# display_zm1325.net
KiCad netlist of a schematic drawn in EAGLE
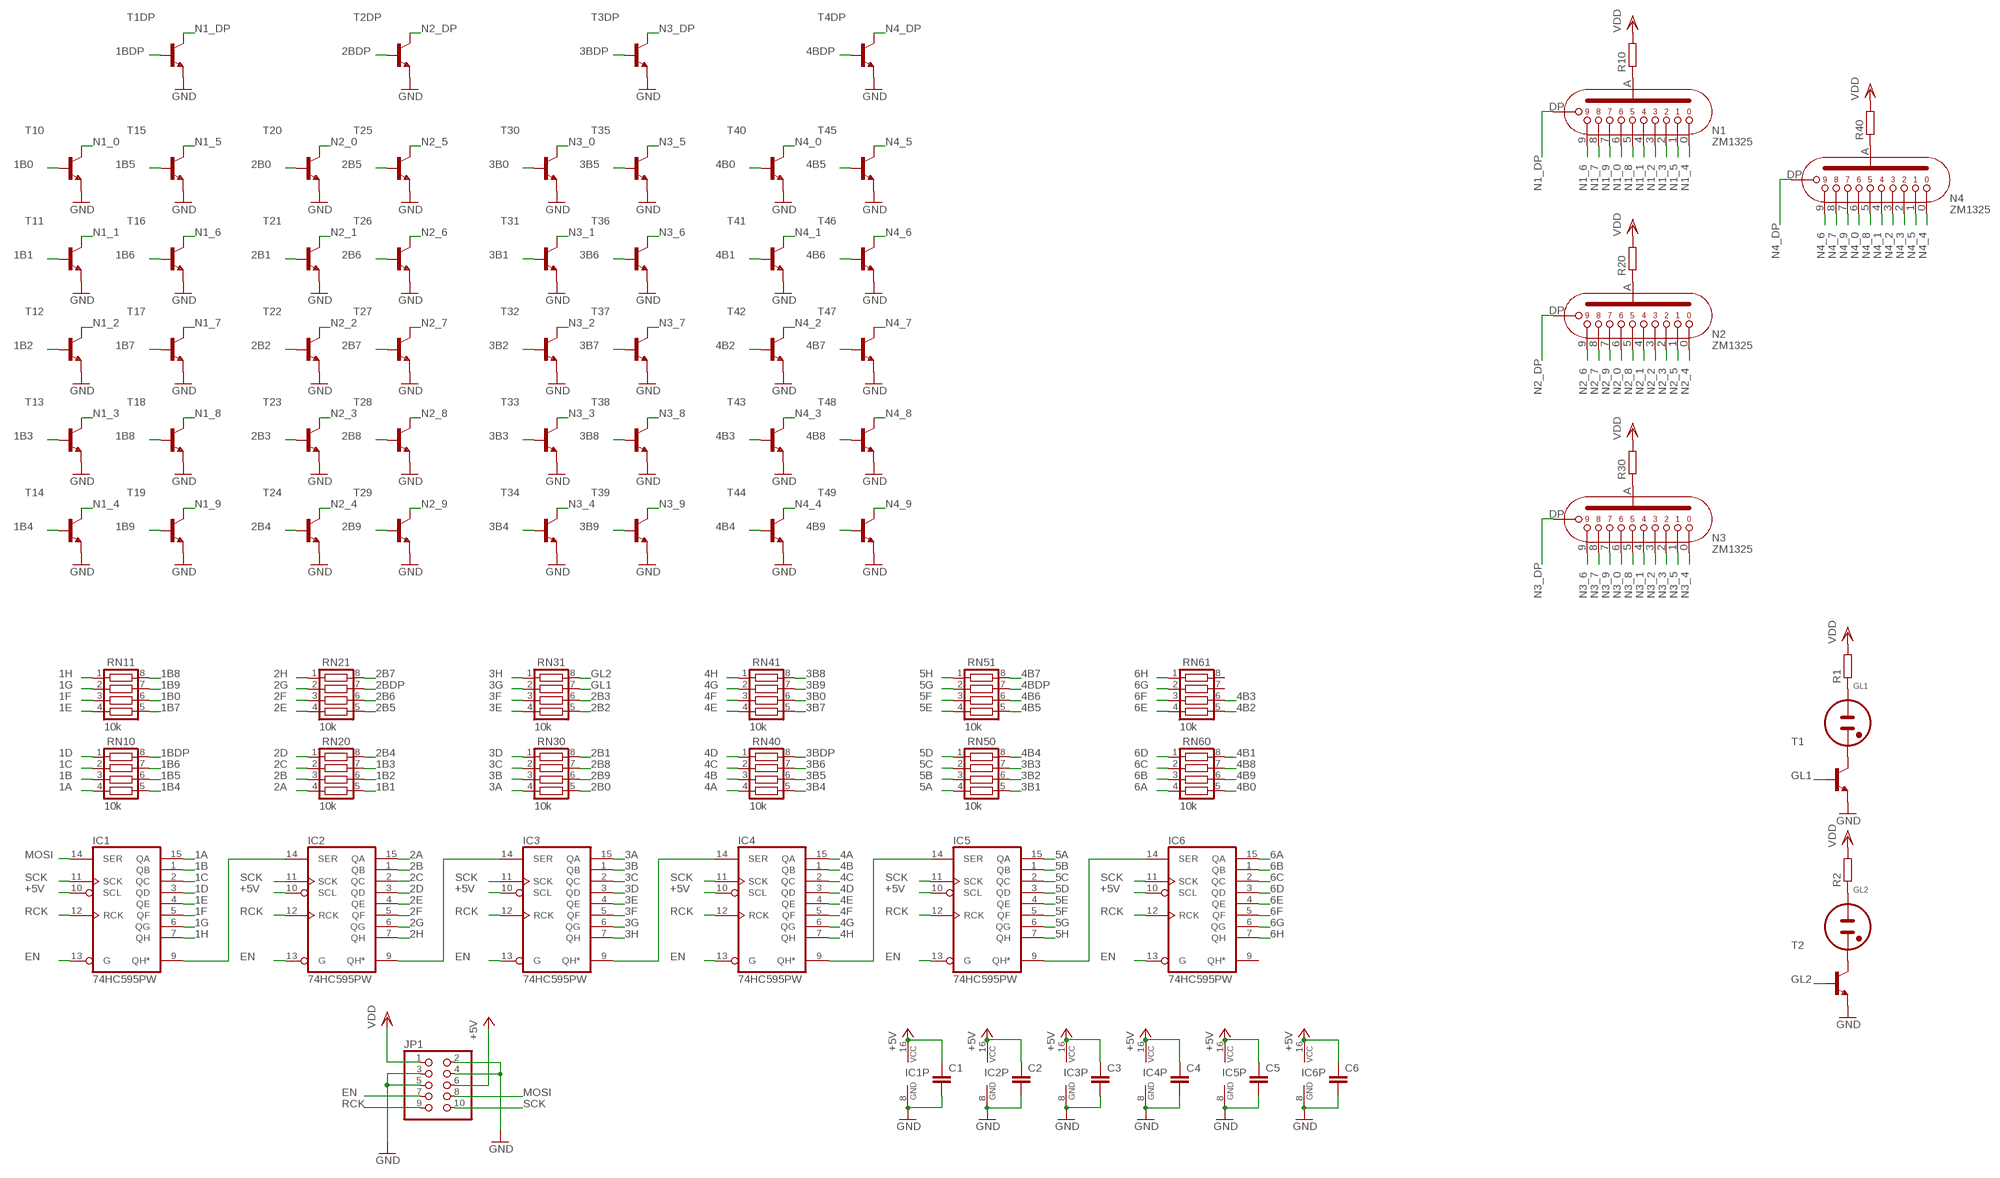
[diagram p0: schematic, sheet 1]

(export (version "E")
  (design (tool "Eeschema 10.0.6"))
  (components
    (comp (ref "C1")
      (value "C-EUC0603")
      (footprint "eagle-import:C0603")
      (libsource (lib "eagle-import") (part "C-EUC0603"))
    )
    (comp (ref "C2")
      (value "C-EUC0603")
      (footprint "eagle-import:C0603")
      (libsource (lib "eagle-import") (part "C-EUC0603"))
    )
    (comp (ref "C3")
      (value "C-EUC0603")
      (footprint "eagle-import:C0603")
      (libsource (lib "eagle-import") (part "C-EUC0603"))
    )
    (comp (ref "C4")
      (value "C-EUC0603")
      (footprint "eagle-import:C0603")
      (libsource (lib "eagle-import") (part "C-EUC0603"))
    )
    (comp (ref "C5")
      (value "C-EUC0603")
      (footprint "eagle-import:C0603")
      (libsource (lib "eagle-import") (part "C-EUC0603"))
    )
    (comp (ref "C6")
      (value "C-EUC0603")
      (footprint "eagle-import:C0603")
      (libsource (lib "eagle-import") (part "C-EUC0603"))
    )
    (comp (ref "GL1")
      (value "NE2-NEON-BULB-DRILL")
      (footprint "eagle-import:NE2-NEON-BULB-DRILL")
      (libsource (lib "eagle-import") (part "NE2-NEON-BULB-DRILL"))
    )
    (comp (ref "GL2")
      (value "NE2-NEON-BULB-DRILL")
      (footprint "eagle-import:NE2-NEON-BULB-DRILL")
      (libsource (lib "eagle-import") (part "NE2-NEON-BULB-DRILL"))
    )
    (comp (ref "IC1")
      (value "74HC595PW")
      (footprint "eagle-import:TSSOP16")
      (libsource (lib "eagle-import") (part "74595PWHC"))
    )
    (comp (ref "IC2")
      (value "74HC595PW")
      (footprint "eagle-import:TSSOP16")
      (libsource (lib "eagle-import") (part "74595PWHC"))
    )
    (comp (ref "IC3")
      (value "74HC595PW")
      (footprint "eagle-import:TSSOP16")
      (libsource (lib "eagle-import") (part "74595PWHC"))
    )
    (comp (ref "IC4")
      (value "74HC595PW")
      (footprint "eagle-import:TSSOP16")
      (libsource (lib "eagle-import") (part "74595PWHC"))
    )
    (comp (ref "IC5")
      (value "74HC595PW")
      (footprint "eagle-import:TSSOP16")
      (libsource (lib "eagle-import") (part "74595PWHC"))
    )
    (comp (ref "IC6")
      (value "74HC595PW")
      (footprint "eagle-import:TSSOP16")
      (libsource (lib "eagle-import") (part "74595PWHC"))
    )
    (comp (ref "JP1")
      (value "PINHD-2X5_2.54-SMD")
      (footprint "eagle-import:2X05SMD")
      (libsource (lib "eagle-import") (part "PINHD-2X5_2.54-SMD"))
    )
    (comp (ref "N1")
      (value "ZM1325")
      (footprint "eagle-import:ZM1325")
      (libsource (lib "eagle-import") (part "ZM1325"))
    )
    (comp (ref "N2")
      (value "ZM1325")
      (footprint "eagle-import:ZM1325")
      (libsource (lib "eagle-import") (part "ZM1325"))
    )
    (comp (ref "N3")
      (value "ZM1325")
      (footprint "eagle-import:ZM1325")
      (libsource (lib "eagle-import") (part "ZM1325"))
    )
    (comp (ref "N4")
      (value "ZM1325")
      (footprint "eagle-import:ZM1325")
      (libsource (lib "eagle-import") (part "ZM1325"))
    )
    (comp (ref "R1")
      (value "R-EU_R0603")
      (footprint "eagle-import:R0603")
      (libsource (lib "eagle-import") (part "R-EU_R0603"))
    )
    (comp (ref "R2")
      (value "R-EU_R0603")
      (footprint "eagle-import:R0603")
      (libsource (lib "eagle-import") (part "R-EU_R0603"))
    )
    (comp (ref "R10")
      (value "R-EU_R0603")
      (footprint "eagle-import:R0603")
      (libsource (lib "eagle-import") (part "R-EU_R0603"))
    )
    (comp (ref "R20")
      (value "R-EU_R0603")
      (footprint "eagle-import:R0603")
      (libsource (lib "eagle-import") (part "R-EU_R0603"))
    )
    (comp (ref "R30")
      (value "R-EU_R0603")
      (footprint "eagle-import:R0603")
      (libsource (lib "eagle-import") (part "R-EU_R0603"))
    )
    (comp (ref "R40")
      (value "R-EU_R0603")
      (footprint "eagle-import:R0603")
      (libsource (lib "eagle-import") (part "R-EU_R0603"))
    )
    (comp (ref "RN10")
      (value "10k")
      (footprint "eagle-import:CTS742C083")
      (fields (field (name "OC_FARNELL") "unknown") (field (name "OC_NEWARK") "unknown"))
      (libsource (lib "eagle-import") (part "CTS742C083"))
    )
    (comp (ref "RN11")
      (value "10k")
      (footprint "eagle-import:CTS742C083")
      (fields (field (name "OC_FARNELL") "unknown") (field (name "OC_NEWARK") "unknown"))
      (libsource (lib "eagle-import") (part "CTS742C083"))
    )
    (comp (ref "RN20")
      (value "10k")
      (footprint "eagle-import:CTS742C083")
      (fields (field (name "OC_FARNELL") "unknown") (field (name "OC_NEWARK") "unknown"))
      (libsource (lib "eagle-import") (part "CTS742C083"))
    )
    (comp (ref "RN21")
      (value "10k")
      (footprint "eagle-import:CTS742C083")
      (fields (field (name "OC_FARNELL") "unknown") (field (name "OC_NEWARK") "unknown"))
      (libsource (lib "eagle-import") (part "CTS742C083"))
    )
    (comp (ref "RN30")
      (value "10k")
      (footprint "eagle-import:CTS742C083")
      (fields (field (name "OC_FARNELL") "unknown") (field (name "OC_NEWARK") "unknown"))
      (libsource (lib "eagle-import") (part "CTS742C083"))
    )
    (comp (ref "RN31")
      (value "10k")
      (footprint "eagle-import:CTS742C083")
      (fields (field (name "OC_FARNELL") "unknown") (field (name "OC_NEWARK") "unknown"))
      (libsource (lib "eagle-import") (part "CTS742C083"))
    )
    (comp (ref "RN40")
      (value "10k")
      (footprint "eagle-import:CTS742C083")
      (fields (field (name "OC_FARNELL") "unknown") (field (name "OC_NEWARK") "unknown"))
      (libsource (lib "eagle-import") (part "CTS742C083"))
    )
    (comp (ref "RN41")
      (value "10k")
      (footprint "eagle-import:CTS742C083")
      (fields (field (name "OC_FARNELL") "unknown") (field (name "OC_NEWARK") "unknown"))
      (libsource (lib "eagle-import") (part "CTS742C083"))
    )
    (comp (ref "RN50")
      (value "10k")
      (footprint "eagle-import:CTS742C083")
      (fields (field (name "OC_FARNELL") "unknown") (field (name "OC_NEWARK") "unknown"))
      (libsource (lib "eagle-import") (part "CTS742C083"))
    )
    (comp (ref "RN51")
      (value "10k")
      (footprint "eagle-import:CTS742C083")
      (fields (field (name "OC_FARNELL") "unknown") (field (name "OC_NEWARK") "unknown"))
      (libsource (lib "eagle-import") (part "CTS742C083"))
    )
    (comp (ref "RN60")
      (value "10k")
      (footprint "eagle-import:CTS742C083")
      (fields (field (name "OC_FARNELL") "unknown") (field (name "OC_NEWARK") "unknown"))
      (libsource (lib "eagle-import") (part "CTS742C083"))
    )
    (comp (ref "RN61")
      (value "10k")
      (footprint "eagle-import:CTS742C083")
      (fields (field (name "OC_FARNELL") "unknown") (field (name "OC_NEWARK") "unknown"))
      (libsource (lib "eagle-import") (part "CTS742C083"))
    )
    (comp (ref "T1")
      (value "SMBTA42")
      (footprint "eagle-import:SOT23")
      (libsource (lib "eagle-import") (part "SMBTA42"))
    )
    (comp (ref "T1DP")
      (value "SMBTA42")
      (footprint "eagle-import:SOT23")
      (libsource (lib "eagle-import") (part "SMBTA42"))
    )
    (comp (ref "T2")
      (value "SMBTA42")
      (footprint "eagle-import:SOT23")
      (libsource (lib "eagle-import") (part "SMBTA42"))
    )
    (comp (ref "T2DP")
      (value "SMBTA42")
      (footprint "eagle-import:SOT23")
      (libsource (lib "eagle-import") (part "SMBTA42"))
    )
    (comp (ref "T3DP")
      (value "SMBTA42")
      (footprint "eagle-import:SOT23")
      (libsource (lib "eagle-import") (part "SMBTA42"))
    )
    (comp (ref "T4DP")
      (value "SMBTA42")
      (footprint "eagle-import:SOT23")
      (libsource (lib "eagle-import") (part "SMBTA42"))
    )
    (comp (ref "T10")
      (value "SMBTA42")
      (footprint "eagle-import:SOT23")
      (libsource (lib "eagle-import") (part "SMBTA42"))
    )
    (comp (ref "T11")
      (value "SMBTA42")
      (footprint "eagle-import:SOT23")
      (libsource (lib "eagle-import") (part "SMBTA42"))
    )
    (comp (ref "T12")
      (value "SMBTA42")
      (footprint "eagle-import:SOT23")
      (libsource (lib "eagle-import") (part "SMBTA42"))
    )
    (comp (ref "T13")
      (value "SMBTA42")
      (footprint "eagle-import:SOT23")
      (libsource (lib "eagle-import") (part "SMBTA42"))
    )
    (comp (ref "T14")
      (value "SMBTA42")
      (footprint "eagle-import:SOT23")
      (libsource (lib "eagle-import") (part "SMBTA42"))
    )
    (comp (ref "T15")
      (value "SMBTA42")
      (footprint "eagle-import:SOT23")
      (libsource (lib "eagle-import") (part "SMBTA42"))
    )
    (comp (ref "T16")
      (value "SMBTA42")
      (footprint "eagle-import:SOT23")
      (libsource (lib "eagle-import") (part "SMBTA42"))
    )
    (comp (ref "T17")
      (value "SMBTA42")
      (footprint "eagle-import:SOT23")
      (libsource (lib "eagle-import") (part "SMBTA42"))
    )
    (comp (ref "T18")
      (value "SMBTA42")
      (footprint "eagle-import:SOT23")
      (libsource (lib "eagle-import") (part "SMBTA42"))
    )
    (comp (ref "T19")
      (value "SMBTA42")
      (footprint "eagle-import:SOT23")
      (libsource (lib "eagle-import") (part "SMBTA42"))
    )
    (comp (ref "T20")
      (value "SMBTA42")
      (footprint "eagle-import:SOT23")
      (libsource (lib "eagle-import") (part "SMBTA42"))
    )
    (comp (ref "T21")
      (value "SMBTA42")
      (footprint "eagle-import:SOT23")
      (libsource (lib "eagle-import") (part "SMBTA42"))
    )
    (comp (ref "T22")
      (value "SMBTA42")
      (footprint "eagle-import:SOT23")
      (libsource (lib "eagle-import") (part "SMBTA42"))
    )
    (comp (ref "T23")
      (value "SMBTA42")
      (footprint "eagle-import:SOT23")
      (libsource (lib "eagle-import") (part "SMBTA42"))
    )
    (comp (ref "T24")
      (value "SMBTA42")
      (footprint "eagle-import:SOT23")
      (libsource (lib "eagle-import") (part "SMBTA42"))
    )
    (comp (ref "T25")
      (value "SMBTA42")
      (footprint "eagle-import:SOT23")
      (libsource (lib "eagle-import") (part "SMBTA42"))
    )
    (comp (ref "T26")
      (value "SMBTA42")
      (footprint "eagle-import:SOT23")
      (libsource (lib "eagle-import") (part "SMBTA42"))
    )
    (comp (ref "T27")
      (value "SMBTA42")
      (footprint "eagle-import:SOT23")
      (libsource (lib "eagle-import") (part "SMBTA42"))
    )
    (comp (ref "T28")
      (value "SMBTA42")
      (footprint "eagle-import:SOT23")
      (libsource (lib "eagle-import") (part "SMBTA42"))
    )
    (comp (ref "T29")
      (value "SMBTA42")
      (footprint "eagle-import:SOT23")
      (libsource (lib "eagle-import") (part "SMBTA42"))
    )
    (comp (ref "T30")
      (value "SMBTA42")
      (footprint "eagle-import:SOT23")
      (libsource (lib "eagle-import") (part "SMBTA42"))
    )
    (comp (ref "T31")
      (value "SMBTA42")
      (footprint "eagle-import:SOT23")
      (libsource (lib "eagle-import") (part "SMBTA42"))
    )
    (comp (ref "T32")
      (value "SMBTA42")
      (footprint "eagle-import:SOT23")
      (libsource (lib "eagle-import") (part "SMBTA42"))
    )
    (comp (ref "T33")
      (value "SMBTA42")
      (footprint "eagle-import:SOT23")
      (libsource (lib "eagle-import") (part "SMBTA42"))
    )
    (comp (ref "T34")
      (value "SMBTA42")
      (footprint "eagle-import:SOT23")
      (libsource (lib "eagle-import") (part "SMBTA42"))
    )
    (comp (ref "T35")
      (value "SMBTA42")
      (footprint "eagle-import:SOT23")
      (libsource (lib "eagle-import") (part "SMBTA42"))
    )
    (comp (ref "T36")
      (value "SMBTA42")
      (footprint "eagle-import:SOT23")
      (libsource (lib "eagle-import") (part "SMBTA42"))
    )
    (comp (ref "T37")
      (value "SMBTA42")
      (footprint "eagle-import:SOT23")
      (libsource (lib "eagle-import") (part "SMBTA42"))
    )
    (comp (ref "T38")
      (value "SMBTA42")
      (footprint "eagle-import:SOT23")
      (libsource (lib "eagle-import") (part "SMBTA42"))
    )
    (comp (ref "T39")
      (value "SMBTA42")
      (footprint "eagle-import:SOT23")
      (libsource (lib "eagle-import") (part "SMBTA42"))
    )
    (comp (ref "T40")
      (value "SMBTA42")
      (footprint "eagle-import:SOT23")
      (libsource (lib "eagle-import") (part "SMBTA42"))
    )
    (comp (ref "T41")
      (value "SMBTA42")
      (footprint "eagle-import:SOT23")
      (libsource (lib "eagle-import") (part "SMBTA42"))
    )
    (comp (ref "T42")
      (value "SMBTA42")
      (footprint "eagle-import:SOT23")
      (libsource (lib "eagle-import") (part "SMBTA42"))
    )
    (comp (ref "T43")
      (value "SMBTA42")
      (footprint "eagle-import:SOT23")
      (libsource (lib "eagle-import") (part "SMBTA42"))
    )
    (comp (ref "T44")
      (value "SMBTA42")
      (footprint "eagle-import:SOT23")
      (libsource (lib "eagle-import") (part "SMBTA42"))
    )
    (comp (ref "T45")
      (value "SMBTA42")
      (footprint "eagle-import:SOT23")
      (libsource (lib "eagle-import") (part "SMBTA42"))
    )
    (comp (ref "T46")
      (value "SMBTA42")
      (footprint "eagle-import:SOT23")
      (libsource (lib "eagle-import") (part "SMBTA42"))
    )
    (comp (ref "T47")
      (value "SMBTA42")
      (footprint "eagle-import:SOT23")
      (libsource (lib "eagle-import") (part "SMBTA42"))
    )
    (comp (ref "T48")
      (value "SMBTA42")
      (footprint "eagle-import:SOT23")
      (libsource (lib "eagle-import") (part "SMBTA42"))
    )
    (comp (ref "T49")
      (value "SMBTA42")
      (footprint "eagle-import:SOT23")
      (libsource (lib "eagle-import") (part "SMBTA42"))
    )
  )
  (nets
    (net (code "1") (name "+5V") (class "Default")
      (node (ref "C1") (pin "1") (pinfunction "1_1") (pintype "passive"))
      (node (ref "C2") (pin "1") (pinfunction "1_1") (pintype "passive"))
      (node (ref "C3") (pin "1") (pinfunction "1_1") (pintype "passive"))
      (node (ref "C4") (pin "1") (pinfunction "1_1") (pintype "passive"))
      (node (ref "C5") (pin "1") (pinfunction "1_1") (pintype "passive"))
      (node (ref "C6") (pin "1") (pinfunction "1_1") (pintype "passive"))
      (node (ref "IC1") (pin "10") (pinfunction "SCL_10") (pintype "input"))
      (node (ref "IC1") (pin "16") (pinfunction "VCC_16") (pintype "power_in"))
      (node (ref "IC2") (pin "10") (pinfunction "SCL_10") (pintype "input"))
      (node (ref "IC2") (pin "16") (pinfunction "VCC_16") (pintype "power_in"))
      (node (ref "IC3") (pin "10") (pinfunction "SCL_10") (pintype "input"))
      (node (ref "IC3") (pin "16") (pinfunction "VCC_16") (pintype "power_in"))
      (node (ref "IC4") (pin "10") (pinfunction "SCL_10") (pintype "input"))
      (node (ref "IC4") (pin "16") (pinfunction "VCC_16") (pintype "power_in"))
      (node (ref "IC5") (pin "10") (pinfunction "SCL_10") (pintype "input"))
      (node (ref "IC5") (pin "16") (pinfunction "VCC_16") (pintype "power_in"))
      (node (ref "IC6") (pin "10") (pinfunction "SCL_10") (pintype "input"))
      (node (ref "IC6") (pin "16") (pinfunction "VCC_16") (pintype "power_in"))
      (node (ref "JP1") (pin "6") (pinfunction "6_6") (pintype "passive"))
    )
    (net (code "2") (name "/1A") (class "Default")
      (node (ref "IC1") (pin "15") (pinfunction "QA_15") (pintype "tri_state"))
      (node (ref "RN10") (pin "4") (pinfunction "4_4") (pintype "passive"))
    )
    (net (code "3") (name "/1B") (class "Default")
      (node (ref "IC1") (pin "1") (pinfunction "QB_1") (pintype "tri_state"))
      (node (ref "RN10") (pin "3") (pinfunction "3_3") (pintype "passive"))
    )
    (net (code "4") (name "/1B0") (class "Default")
      (node (ref "RN11") (pin "6") (pinfunction "6_6") (pintype "passive"))
      (node (ref "T10") (pin "1") (pinfunction "B_1") (pintype "passive"))
    )
    (net (code "5") (name "/1B1") (class "Default")
      (node (ref "RN20") (pin "5") (pinfunction "5_5") (pintype "passive"))
      (node (ref "T11") (pin "1") (pinfunction "B_1") (pintype "passive"))
    )
    (net (code "6") (name "/1B2") (class "Default")
      (node (ref "RN20") (pin "6") (pinfunction "6_6") (pintype "passive"))
      (node (ref "T12") (pin "1") (pinfunction "B_1") (pintype "passive"))
    )
    (net (code "7") (name "/1B3") (class "Default")
      (node (ref "RN20") (pin "7") (pinfunction "7_7") (pintype "passive"))
      (node (ref "T13") (pin "1") (pinfunction "B_1") (pintype "passive"))
    )
    (net (code "8") (name "/1B4") (class "Default")
      (node (ref "RN10") (pin "5") (pinfunction "5_5") (pintype "passive"))
      (node (ref "T14") (pin "1") (pinfunction "B_1") (pintype "passive"))
    )
    (net (code "9") (name "/1B5") (class "Default")
      (node (ref "RN10") (pin "6") (pinfunction "6_6") (pintype "passive"))
      (node (ref "T15") (pin "1") (pinfunction "B_1") (pintype "passive"))
    )
    (net (code "10") (name "/1B6") (class "Default")
      (node (ref "RN10") (pin "7") (pinfunction "7_7") (pintype "passive"))
      (node (ref "T16") (pin "1") (pinfunction "B_1") (pintype "passive"))
    )
    (net (code "11") (name "/1B7") (class "Default")
      (node (ref "RN11") (pin "5") (pinfunction "5_5") (pintype "passive"))
      (node (ref "T17") (pin "1") (pinfunction "B_1") (pintype "passive"))
    )
    (net (code "12") (name "/1B8") (class "Default")
      (node (ref "RN11") (pin "8") (pinfunction "8_8") (pintype "passive"))
      (node (ref "T18") (pin "1") (pinfunction "B_1") (pintype "passive"))
    )
    (net (code "13") (name "/1B9") (class "Default")
      (node (ref "RN11") (pin "7") (pinfunction "7_7") (pintype "passive"))
      (node (ref "T19") (pin "1") (pinfunction "B_1") (pintype "passive"))
    )
    (net (code "14") (name "/1BDP") (class "Default")
      (node (ref "RN10") (pin "8") (pinfunction "8_8") (pintype "passive"))
      (node (ref "T1DP") (pin "1") (pinfunction "B_1") (pintype "passive"))
    )
    (net (code "15") (name "/1C") (class "Default")
      (node (ref "IC1") (pin "2") (pinfunction "QC_2") (pintype "tri_state"))
      (node (ref "RN10") (pin "2") (pinfunction "2_2") (pintype "passive"))
    )
    (net (code "16") (name "/1D") (class "Default")
      (node (ref "IC1") (pin "3") (pinfunction "QD_3") (pintype "tri_state"))
      (node (ref "RN10") (pin "1") (pinfunction "1_1") (pintype "passive"))
    )
    (net (code "17") (name "/1E") (class "Default")
      (node (ref "IC1") (pin "4") (pinfunction "QE_4") (pintype "tri_state"))
      (node (ref "RN11") (pin "4") (pinfunction "4_4") (pintype "passive"))
    )
    (net (code "18") (name "/1F") (class "Default")
      (node (ref "IC1") (pin "5") (pinfunction "QF_5") (pintype "tri_state"))
      (node (ref "RN11") (pin "3") (pinfunction "3_3") (pintype "passive"))
    )
    (net (code "19") (name "/1G") (class "Default")
      (node (ref "IC1") (pin "6") (pinfunction "QG_6") (pintype "tri_state"))
      (node (ref "RN11") (pin "2") (pinfunction "2_2") (pintype "passive"))
    )
    (net (code "20") (name "/1H") (class "Default")
      (node (ref "IC1") (pin "7") (pinfunction "QH_7") (pintype "tri_state"))
      (node (ref "RN11") (pin "1") (pinfunction "1_1") (pintype "passive"))
    )
    (net (code "21") (name "/2A") (class "Default")
      (node (ref "IC2") (pin "15") (pinfunction "QA_15") (pintype "tri_state"))
      (node (ref "RN20") (pin "4") (pinfunction "4_4") (pintype "passive"))
    )
    (net (code "22") (name "/2B") (class "Default")
      (node (ref "IC2") (pin "1") (pinfunction "QB_1") (pintype "tri_state"))
      (node (ref "RN20") (pin "3") (pinfunction "3_3") (pintype "passive"))
    )
    (net (code "23") (name "/2B0") (class "Default")
      (node (ref "RN30") (pin "5") (pinfunction "5_5") (pintype "passive"))
      (node (ref "T20") (pin "1") (pinfunction "B_1") (pintype "passive"))
    )
    (net (code "24") (name "/2B1") (class "Default")
      (node (ref "RN30") (pin "8") (pinfunction "8_8") (pintype "passive"))
      (node (ref "T21") (pin "1") (pinfunction "B_1") (pintype "passive"))
    )
    (net (code "25") (name "/2B2") (class "Default")
      (node (ref "RN31") (pin "5") (pinfunction "5_5") (pintype "passive"))
      (node (ref "T22") (pin "1") (pinfunction "B_1") (pintype "passive"))
    )
    (net (code "26") (name "/2B3") (class "Default")
      (node (ref "RN31") (pin "6") (pinfunction "6_6") (pintype "passive"))
      (node (ref "T23") (pin "1") (pinfunction "B_1") (pintype "passive"))
    )
    (net (code "27") (name "/2B4") (class "Default")
      (node (ref "RN20") (pin "8") (pinfunction "8_8") (pintype "passive"))
      (node (ref "T24") (pin "1") (pinfunction "B_1") (pintype "passive"))
    )
    (net (code "28") (name "/2B5") (class "Default")
      (node (ref "RN21") (pin "5") (pinfunction "5_5") (pintype "passive"))
      (node (ref "T25") (pin "1") (pinfunction "B_1") (pintype "passive"))
    )
    (net (code "29") (name "/2B6") (class "Default")
      (node (ref "RN21") (pin "6") (pinfunction "6_6") (pintype "passive"))
      (node (ref "T26") (pin "1") (pinfunction "B_1") (pintype "passive"))
    )
    (net (code "30") (name "/2B7") (class "Default")
      (node (ref "RN21") (pin "8") (pinfunction "8_8") (pintype "passive"))
      (node (ref "T27") (pin "1") (pinfunction "B_1") (pintype "passive"))
    )
    (net (code "31") (name "/2B8") (class "Default")
      (node (ref "RN30") (pin "7") (pinfunction "7_7") (pintype "passive"))
      (node (ref "T28") (pin "1") (pinfunction "B_1") (pintype "passive"))
    )
    (net (code "32") (name "/2B9") (class "Default")
      (node (ref "RN30") (pin "6") (pinfunction "6_6") (pintype "passive"))
      (node (ref "T29") (pin "1") (pinfunction "B_1") (pintype "passive"))
    )
    (net (code "33") (name "/2BDP") (class "Default")
      (node (ref "RN21") (pin "7") (pinfunction "7_7") (pintype "passive"))
      (node (ref "T2DP") (pin "1") (pinfunction "B_1") (pintype "passive"))
    )
    (net (code "34") (name "/2C") (class "Default")
      (node (ref "IC2") (pin "2") (pinfunction "QC_2") (pintype "tri_state"))
      (node (ref "RN20") (pin "2") (pinfunction "2_2") (pintype "passive"))
    )
    (net (code "35") (name "/2D") (class "Default")
      (node (ref "IC2") (pin "3") (pinfunction "QD_3") (pintype "tri_state"))
      (node (ref "RN20") (pin "1") (pinfunction "1_1") (pintype "passive"))
    )
    (net (code "36") (name "/2E") (class "Default")
      (node (ref "IC2") (pin "4") (pinfunction "QE_4") (pintype "tri_state"))
      (node (ref "RN21") (pin "4") (pinfunction "4_4") (pintype "passive"))
    )
    (net (code "37") (name "/2F") (class "Default")
      (node (ref "IC2") (pin "5") (pinfunction "QF_5") (pintype "tri_state"))
      (node (ref "RN21") (pin "3") (pinfunction "3_3") (pintype "passive"))
    )
    (net (code "38") (name "/2G") (class "Default")
      (node (ref "IC2") (pin "6") (pinfunction "QG_6") (pintype "tri_state"))
      (node (ref "RN21") (pin "2") (pinfunction "2_2") (pintype "passive"))
    )
    (net (code "39") (name "/2H") (class "Default")
      (node (ref "IC2") (pin "7") (pinfunction "QH_7") (pintype "tri_state"))
      (node (ref "RN21") (pin "1") (pinfunction "1_1") (pintype "passive"))
    )
    (net (code "40") (name "/3A") (class "Default")
      (node (ref "IC3") (pin "15") (pinfunction "QA_15") (pintype "tri_state"))
      (node (ref "RN30") (pin "4") (pinfunction "4_4") (pintype "passive"))
    )
    (net (code "41") (name "/3B") (class "Default")
      (node (ref "IC3") (pin "1") (pinfunction "QB_1") (pintype "tri_state"))
      (node (ref "RN30") (pin "3") (pinfunction "3_3") (pintype "passive"))
    )
    (net (code "42") (name "/3B0") (class "Default")
      (node (ref "RN41") (pin "6") (pinfunction "6_6") (pintype "passive"))
      (node (ref "T30") (pin "1") (pinfunction "B_1") (pintype "passive"))
    )
    (net (code "43") (name "/3B1") (class "Default")
      (node (ref "RN50") (pin "5") (pinfunction "5_5") (pintype "passive"))
      (node (ref "T31") (pin "1") (pinfunction "B_1") (pintype "passive"))
    )
    (net (code "44") (name "/3B2") (class "Default")
      (node (ref "RN50") (pin "6") (pinfunction "6_6") (pintype "passive"))
      (node (ref "T32") (pin "1") (pinfunction "B_1") (pintype "passive"))
    )
    (net (code "45") (name "/3B3") (class "Default")
      (node (ref "RN50") (pin "7") (pinfunction "7_7") (pintype "passive"))
      (node (ref "T33") (pin "1") (pinfunction "B_1") (pintype "passive"))
    )
    (net (code "46") (name "/3B4") (class "Default")
      (node (ref "RN40") (pin "5") (pinfunction "5_5") (pintype "passive"))
      (node (ref "T34") (pin "1") (pinfunction "B_1") (pintype "passive"))
    )
    (net (code "47") (name "/3B5") (class "Default")
      (node (ref "RN40") (pin "6") (pinfunction "6_6") (pintype "passive"))
      (node (ref "T35") (pin "1") (pinfunction "B_1") (pintype "passive"))
    )
    (net (code "48") (name "/3B6") (class "Default")
      (node (ref "RN40") (pin "7") (pinfunction "7_7") (pintype "passive"))
      (node (ref "T36") (pin "1") (pinfunction "B_1") (pintype "passive"))
    )
    (net (code "49") (name "/3B7") (class "Default")
      (node (ref "RN41") (pin "5") (pinfunction "5_5") (pintype "passive"))
      (node (ref "T37") (pin "1") (pinfunction "B_1") (pintype "passive"))
    )
    (net (code "50") (name "/3B8") (class "Default")
      (node (ref "RN41") (pin "8") (pinfunction "8_8") (pintype "passive"))
      (node (ref "T38") (pin "1") (pinfunction "B_1") (pintype "passive"))
    )
    (net (code "51") (name "/3B9") (class "Default")
      (node (ref "RN41") (pin "7") (pinfunction "7_7") (pintype "passive"))
      (node (ref "T39") (pin "1") (pinfunction "B_1") (pintype "passive"))
    )
    (net (code "52") (name "/3BDP") (class "Default")
      (node (ref "RN40") (pin "8") (pinfunction "8_8") (pintype "passive"))
      (node (ref "T3DP") (pin "1") (pinfunction "B_1") (pintype "passive"))
    )
    (net (code "53") (name "/3C") (class "Default")
      (node (ref "IC3") (pin "2") (pinfunction "QC_2") (pintype "tri_state"))
      (node (ref "RN30") (pin "2") (pinfunction "2_2") (pintype "passive"))
    )
    (net (code "54") (name "/3D") (class "Default")
      (node (ref "IC3") (pin "3") (pinfunction "QD_3") (pintype "tri_state"))
      (node (ref "RN30") (pin "1") (pinfunction "1_1") (pintype "passive"))
    )
    (net (code "55") (name "/3E") (class "Default")
      (node (ref "IC3") (pin "4") (pinfunction "QE_4") (pintype "tri_state"))
      (node (ref "RN31") (pin "4") (pinfunction "4_4") (pintype "passive"))
    )
    (net (code "56") (name "/3F") (class "Default")
      (node (ref "IC3") (pin "5") (pinfunction "QF_5") (pintype "tri_state"))
      (node (ref "RN31") (pin "3") (pinfunction "3_3") (pintype "passive"))
    )
    (net (code "57") (name "/3G") (class "Default")
      (node (ref "IC3") (pin "6") (pinfunction "QG_6") (pintype "tri_state"))
      (node (ref "RN31") (pin "2") (pinfunction "2_2") (pintype "passive"))
    )
    (net (code "58") (name "/3H") (class "Default")
      (node (ref "IC3") (pin "7") (pinfunction "QH_7") (pintype "tri_state"))
      (node (ref "RN31") (pin "1") (pinfunction "1_1") (pintype "passive"))
    )
    (net (code "59") (name "/4A") (class "Default")
      (node (ref "IC4") (pin "15") (pinfunction "QA_15") (pintype "tri_state"))
      (node (ref "RN40") (pin "4") (pinfunction "4_4") (pintype "passive"))
    )
    (net (code "60") (name "/4B") (class "Default")
      (node (ref "IC4") (pin "1") (pinfunction "QB_1") (pintype "tri_state"))
      (node (ref "RN40") (pin "3") (pinfunction "3_3") (pintype "passive"))
    )
    (net (code "61") (name "/4B0") (class "Default")
      (node (ref "RN60") (pin "5") (pinfunction "5_5") (pintype "passive"))
      (node (ref "T40") (pin "1") (pinfunction "B_1") (pintype "passive"))
    )
    (net (code "62") (name "/4B1") (class "Default")
      (node (ref "RN60") (pin "8") (pinfunction "8_8") (pintype "passive"))
      (node (ref "T41") (pin "1") (pinfunction "B_1") (pintype "passive"))
    )
    (net (code "63") (name "/4B2") (class "Default")
      (node (ref "RN61") (pin "5") (pinfunction "5_5") (pintype "passive"))
      (node (ref "T42") (pin "1") (pinfunction "B_1") (pintype "passive"))
    )
    (net (code "64") (name "/4B3") (class "Default")
      (node (ref "RN61") (pin "6") (pinfunction "6_6") (pintype "passive"))
      (node (ref "T43") (pin "1") (pinfunction "B_1") (pintype "passive"))
    )
    (net (code "65") (name "/4B4") (class "Default")
      (node (ref "RN50") (pin "8") (pinfunction "8_8") (pintype "passive"))
      (node (ref "T44") (pin "1") (pinfunction "B_1") (pintype "passive"))
    )
    (net (code "66") (name "/4B5") (class "Default")
      (node (ref "RN51") (pin "5") (pinfunction "5_5") (pintype "passive"))
      (node (ref "T45") (pin "1") (pinfunction "B_1") (pintype "passive"))
    )
    (net (code "67") (name "/4B6") (class "Default")
      (node (ref "RN51") (pin "6") (pinfunction "6_6") (pintype "passive"))
      (node (ref "T46") (pin "1") (pinfunction "B_1") (pintype "passive"))
    )
    (net (code "68") (name "/4B7") (class "Default")
      (node (ref "RN51") (pin "8") (pinfunction "8_8") (pintype "passive"))
      (node (ref "T47") (pin "1") (pinfunction "B_1") (pintype "passive"))
    )
    (net (code "69") (name "/4B8") (class "Default")
      (node (ref "RN60") (pin "7") (pinfunction "7_7") (pintype "passive"))
      (node (ref "T48") (pin "1") (pinfunction "B_1") (pintype "passive"))
    )
    (net (code "70") (name "/4B9") (class "Default")
      (node (ref "RN60") (pin "6") (pinfunction "6_6") (pintype "passive"))
      (node (ref "T49") (pin "1") (pinfunction "B_1") (pintype "passive"))
    )
    (net (code "71") (name "/4BDP") (class "Default")
      (node (ref "RN51") (pin "7") (pinfunction "7_7") (pintype "passive"))
      (node (ref "T4DP") (pin "1") (pinfunction "B_1") (pintype "passive"))
    )
    (net (code "72") (name "/4C") (class "Default")
      (node (ref "IC4") (pin "2") (pinfunction "QC_2") (pintype "tri_state"))
      (node (ref "RN40") (pin "2") (pinfunction "2_2") (pintype "passive"))
    )
    (net (code "73") (name "/4D") (class "Default")
      (node (ref "IC4") (pin "3") (pinfunction "QD_3") (pintype "tri_state"))
      (node (ref "RN40") (pin "1") (pinfunction "1_1") (pintype "passive"))
    )
    (net (code "74") (name "/4E") (class "Default")
      (node (ref "IC4") (pin "4") (pinfunction "QE_4") (pintype "tri_state"))
      (node (ref "RN41") (pin "4") (pinfunction "4_4") (pintype "passive"))
    )
    (net (code "75") (name "/4F") (class "Default")
      (node (ref "IC4") (pin "5") (pinfunction "QF_5") (pintype "tri_state"))
      (node (ref "RN41") (pin "3") (pinfunction "3_3") (pintype "passive"))
    )
    (net (code "76") (name "/4G") (class "Default")
      (node (ref "IC4") (pin "6") (pinfunction "QG_6") (pintype "tri_state"))
      (node (ref "RN41") (pin "2") (pinfunction "2_2") (pintype "passive"))
    )
    (net (code "77") (name "/4H") (class "Default")
      (node (ref "IC4") (pin "7") (pinfunction "QH_7") (pintype "tri_state"))
      (node (ref "RN41") (pin "1") (pinfunction "1_1") (pintype "passive"))
    )
    (net (code "78") (name "/5A") (class "Default")
      (node (ref "IC5") (pin "15") (pinfunction "QA_15") (pintype "tri_state"))
      (node (ref "RN50") (pin "4") (pinfunction "4_4") (pintype "passive"))
    )
    (net (code "79") (name "/5B") (class "Default")
      (node (ref "IC5") (pin "1") (pinfunction "QB_1") (pintype "tri_state"))
      (node (ref "RN50") (pin "3") (pinfunction "3_3") (pintype "passive"))
    )
    (net (code "80") (name "/5C") (class "Default")
      (node (ref "IC5") (pin "2") (pinfunction "QC_2") (pintype "tri_state"))
      (node (ref "RN50") (pin "2") (pinfunction "2_2") (pintype "passive"))
    )
    (net (code "81") (name "/5D") (class "Default")
      (node (ref "IC5") (pin "3") (pinfunction "QD_3") (pintype "tri_state"))
      (node (ref "RN50") (pin "1") (pinfunction "1_1") (pintype "passive"))
    )
    (net (code "82") (name "/5E") (class "Default")
      (node (ref "IC5") (pin "4") (pinfunction "QE_4") (pintype "tri_state"))
      (node (ref "RN51") (pin "4") (pinfunction "4_4") (pintype "passive"))
    )
    (net (code "83") (name "/5F") (class "Default")
      (node (ref "IC5") (pin "5") (pinfunction "QF_5") (pintype "tri_state"))
      (node (ref "RN51") (pin "3") (pinfunction "3_3") (pintype "passive"))
    )
    (net (code "84") (name "/5G") (class "Default")
      (node (ref "IC5") (pin "6") (pinfunction "QG_6") (pintype "tri_state"))
      (node (ref "RN51") (pin "2") (pinfunction "2_2") (pintype "passive"))
    )
    (net (code "85") (name "/5H") (class "Default")
      (node (ref "IC5") (pin "7") (pinfunction "QH_7") (pintype "tri_state"))
      (node (ref "RN51") (pin "1") (pinfunction "1_1") (pintype "passive"))
    )
    (net (code "86") (name "/6A") (class "Default")
      (node (ref "IC6") (pin "15") (pinfunction "QA_15") (pintype "tri_state"))
      (node (ref "RN60") (pin "4") (pinfunction "4_4") (pintype "passive"))
    )
    (net (code "87") (name "/6B") (class "Default")
      (node (ref "IC6") (pin "1") (pinfunction "QB_1") (pintype "tri_state"))
      (node (ref "RN60") (pin "3") (pinfunction "3_3") (pintype "passive"))
    )
    (net (code "88") (name "/6C") (class "Default")
      (node (ref "IC6") (pin "2") (pinfunction "QC_2") (pintype "tri_state"))
      (node (ref "RN60") (pin "2") (pinfunction "2_2") (pintype "passive"))
    )
    (net (code "89") (name "/6D") (class "Default")
      (node (ref "IC6") (pin "3") (pinfunction "QD_3") (pintype "tri_state"))
      (node (ref "RN60") (pin "1") (pinfunction "1_1") (pintype "passive"))
    )
    (net (code "90") (name "/6E") (class "Default")
      (node (ref "IC6") (pin "4") (pinfunction "QE_4") (pintype "tri_state"))
      (node (ref "RN61") (pin "4") (pinfunction "4_4") (pintype "passive"))
    )
    (net (code "91") (name "/6F") (class "Default")
      (node (ref "IC6") (pin "5") (pinfunction "QF_5") (pintype "tri_state"))
      (node (ref "RN61") (pin "3") (pinfunction "3_3") (pintype "passive"))
    )
    (net (code "92") (name "/6G") (class "Default")
      (node (ref "IC6") (pin "6") (pinfunction "QG_6") (pintype "tri_state"))
      (node (ref "RN61") (pin "2") (pinfunction "2_2") (pintype "passive"))
    )
    (net (code "93") (name "/6H") (class "Default")
      (node (ref "IC6") (pin "7") (pinfunction "QH_7") (pintype "tri_state"))
      (node (ref "RN61") (pin "1") (pinfunction "1_1") (pintype "passive"))
    )
    (net (code "94") (name "/EN") (class "Default")
      (node (ref "IC1") (pin "13") (pinfunction "G_13") (pintype "input"))
      (node (ref "IC2") (pin "13") (pinfunction "G_13") (pintype "input"))
      (node (ref "IC3") (pin "13") (pinfunction "G_13") (pintype "input"))
      (node (ref "IC4") (pin "13") (pinfunction "G_13") (pintype "input"))
      (node (ref "IC5") (pin "13") (pinfunction "G_13") (pintype "input"))
      (node (ref "IC6") (pin "13") (pinfunction "G_13") (pintype "input"))
      (node (ref "JP1") (pin "7") (pinfunction "7_7") (pintype "passive"))
    )
    (net (code "95") (name "/GL1") (class "Default")
      (node (ref "RN31") (pin "7") (pinfunction "7_7") (pintype "passive"))
      (node (ref "T1") (pin "1") (pinfunction "B_1") (pintype "passive"))
    )
    (net (code "96") (name "/GL2") (class "Default")
      (node (ref "RN31") (pin "8") (pinfunction "8_8") (pintype "passive"))
      (node (ref "T2") (pin "1") (pinfunction "B_1") (pintype "passive"))
    )
    (net (code "97") (name "/MOSI") (class "Default")
      (node (ref "IC1") (pin "14") (pinfunction "SER_14") (pintype "input"))
      (node (ref "JP1") (pin "8") (pinfunction "8_8") (pintype "passive"))
    )
    (net (code "98") (name "/N1_0") (class "Default")
      (node (ref "N1") (pin "K6") (pinfunction "6_K6") (pintype "bidirectional"))
      (node (ref "T10") (pin "3") (pinfunction "C_3") (pintype "passive"))
    )
    (net (code "99") (name "/N1_1") (class "Default")
      (node (ref "N1") (pin "K4") (pinfunction "4_K4") (pintype "bidirectional"))
      (node (ref "T11") (pin "3") (pinfunction "C_3") (pintype "passive"))
    )
    (net (code "100") (name "/N1_2") (class "Default")
      (node (ref "N1") (pin "K3") (pinfunction "3_K3") (pintype "bidirectional"))
      (node (ref "T12") (pin "3") (pinfunction "C_3") (pintype "passive"))
    )
    (net (code "101") (name "/N1_3") (class "Default")
      (node (ref "N1") (pin "K2") (pinfunction "2_K2") (pintype "bidirectional"))
      (node (ref "T13") (pin "3") (pinfunction "C_3") (pintype "passive"))
    )
    (net (code "102") (name "/N1_4") (class "Default")
      (node (ref "N1") (pin "K0") (pinfunction "0_K0") (pintype "bidirectional"))
      (node (ref "T14") (pin "3") (pinfunction "C_3") (pintype "passive"))
    )
    (net (code "103") (name "/N1_5") (class "Default")
      (node (ref "N1") (pin "K1") (pinfunction "1_K1") (pintype "bidirectional"))
      (node (ref "T15") (pin "3") (pinfunction "C_3") (pintype "passive"))
    )
    (net (code "104") (name "/N1_6") (class "Default")
      (node (ref "N1") (pin "K9") (pinfunction "9_K9") (pintype "bidirectional"))
      (node (ref "T16") (pin "3") (pinfunction "C_3") (pintype "passive"))
    )
    (net (code "105") (name "/N1_7") (class "Default")
      (node (ref "N1") (pin "K8") (pinfunction "8_K8") (pintype "bidirectional"))
      (node (ref "T17") (pin "3") (pinfunction "C_3") (pintype "passive"))
    )
    (net (code "106") (name "/N1_8") (class "Default")
      (node (ref "N1") (pin "K5") (pinfunction "5_K5") (pintype "bidirectional"))
      (node (ref "T18") (pin "3") (pinfunction "C_3") (pintype "passive"))
    )
    (net (code "107") (name "/N1_9") (class "Default")
      (node (ref "N1") (pin "K7") (pinfunction "7_K7") (pintype "bidirectional"))
      (node (ref "T19") (pin "3") (pinfunction "C_3") (pintype "passive"))
    )
    (net (code "108") (name "/N1_DP") (class "Default")
      (node (ref "N1") (pin "KDP") (pinfunction "DP_KDP") (pintype "bidirectional"))
      (node (ref "T1DP") (pin "3") (pinfunction "C_3") (pintype "passive"))
    )
    (net (code "109") (name "/N2_0") (class "Default")
      (node (ref "N2") (pin "K6") (pinfunction "6_K6") (pintype "bidirectional"))
      (node (ref "T20") (pin "3") (pinfunction "C_3") (pintype "passive"))
    )
    (net (code "110") (name "/N2_1") (class "Default")
      (node (ref "N2") (pin "K4") (pinfunction "4_K4") (pintype "bidirectional"))
      (node (ref "T21") (pin "3") (pinfunction "C_3") (pintype "passive"))
    )
    (net (code "111") (name "/N2_2") (class "Default")
      (node (ref "N2") (pin "K3") (pinfunction "3_K3") (pintype "bidirectional"))
      (node (ref "T22") (pin "3") (pinfunction "C_3") (pintype "passive"))
    )
    (net (code "112") (name "/N2_3") (class "Default")
      (node (ref "N2") (pin "K2") (pinfunction "2_K2") (pintype "bidirectional"))
      (node (ref "T23") (pin "3") (pinfunction "C_3") (pintype "passive"))
    )
    (net (code "113") (name "/N2_4") (class "Default")
      (node (ref "N2") (pin "K0") (pinfunction "0_K0") (pintype "bidirectional"))
      (node (ref "T24") (pin "3") (pinfunction "C_3") (pintype "passive"))
    )
    (net (code "114") (name "/N2_5") (class "Default")
      (node (ref "N2") (pin "K1") (pinfunction "1_K1") (pintype "bidirectional"))
      (node (ref "T25") (pin "3") (pinfunction "C_3") (pintype "passive"))
    )
    (net (code "115") (name "/N2_6") (class "Default")
      (node (ref "N2") (pin "K9") (pinfunction "9_K9") (pintype "bidirectional"))
      (node (ref "T26") (pin "3") (pinfunction "C_3") (pintype "passive"))
    )
    (net (code "116") (name "/N2_7") (class "Default")
      (node (ref "N2") (pin "K8") (pinfunction "8_K8") (pintype "bidirectional"))
      (node (ref "T27") (pin "3") (pinfunction "C_3") (pintype "passive"))
    )
    (net (code "117") (name "/N2_8") (class "Default")
      (node (ref "N2") (pin "K5") (pinfunction "5_K5") (pintype "bidirectional"))
      (node (ref "T28") (pin "3") (pinfunction "C_3") (pintype "passive"))
    )
    (net (code "118") (name "/N2_9") (class "Default")
      (node (ref "N2") (pin "K7") (pinfunction "7_K7") (pintype "bidirectional"))
      (node (ref "T29") (pin "3") (pinfunction "C_3") (pintype "passive"))
    )
    (net (code "119") (name "/N2_DP") (class "Default")
      (node (ref "N2") (pin "KDP") (pinfunction "DP_KDP") (pintype "bidirectional"))
      (node (ref "T2DP") (pin "3") (pinfunction "C_3") (pintype "passive"))
    )
    (net (code "120") (name "/N3_0") (class "Default")
      (node (ref "N3") (pin "K6") (pinfunction "6_K6") (pintype "bidirectional"))
      (node (ref "T30") (pin "3") (pinfunction "C_3") (pintype "passive"))
    )
    (net (code "121") (name "/N3_1") (class "Default")
      (node (ref "N3") (pin "K4") (pinfunction "4_K4") (pintype "bidirectional"))
      (node (ref "T31") (pin "3") (pinfunction "C_3") (pintype "passive"))
    )
    (net (code "122") (name "/N3_2") (class "Default")
      (node (ref "N3") (pin "K3") (pinfunction "3_K3") (pintype "bidirectional"))
      (node (ref "T32") (pin "3") (pinfunction "C_3") (pintype "passive"))
    )
    (net (code "123") (name "/N3_3") (class "Default")
      (node (ref "N3") (pin "K2") (pinfunction "2_K2") (pintype "bidirectional"))
      (node (ref "T33") (pin "3") (pinfunction "C_3") (pintype "passive"))
    )
    (net (code "124") (name "/N3_4") (class "Default")
      (node (ref "N3") (pin "K0") (pinfunction "0_K0") (pintype "bidirectional"))
      (node (ref "T34") (pin "3") (pinfunction "C_3") (pintype "passive"))
    )
    (net (code "125") (name "/N3_5") (class "Default")
      (node (ref "N3") (pin "K1") (pinfunction "1_K1") (pintype "bidirectional"))
      (node (ref "T35") (pin "3") (pinfunction "C_3") (pintype "passive"))
    )
    (net (code "126") (name "/N3_6") (class "Default")
      (node (ref "N3") (pin "K9") (pinfunction "9_K9") (pintype "bidirectional"))
      (node (ref "T36") (pin "3") (pinfunction "C_3") (pintype "passive"))
    )
    (net (code "127") (name "/N3_7") (class "Default")
      (node (ref "N3") (pin "K8") (pinfunction "8_K8") (pintype "bidirectional"))
      (node (ref "T37") (pin "3") (pinfunction "C_3") (pintype "passive"))
    )
    (net (code "128") (name "/N3_8") (class "Default")
      (node (ref "N3") (pin "K5") (pinfunction "5_K5") (pintype "bidirectional"))
      (node (ref "T38") (pin "3") (pinfunction "C_3") (pintype "passive"))
    )
    (net (code "129") (name "/N3_9") (class "Default")
      (node (ref "N3") (pin "K7") (pinfunction "7_K7") (pintype "bidirectional"))
      (node (ref "T39") (pin "3") (pinfunction "C_3") (pintype "passive"))
    )
    (net (code "130") (name "/N3_DP") (class "Default")
      (node (ref "N3") (pin "KDP") (pinfunction "DP_KDP") (pintype "bidirectional"))
      (node (ref "T3DP") (pin "3") (pinfunction "C_3") (pintype "passive"))
    )
    (net (code "131") (name "/N4_0") (class "Default")
      (node (ref "N4") (pin "K6") (pinfunction "6_K6") (pintype "bidirectional"))
      (node (ref "T40") (pin "3") (pinfunction "C_3") (pintype "passive"))
    )
    (net (code "132") (name "/N4_1") (class "Default")
      (node (ref "N4") (pin "K4") (pinfunction "4_K4") (pintype "bidirectional"))
      (node (ref "T41") (pin "3") (pinfunction "C_3") (pintype "passive"))
    )
    (net (code "133") (name "/N4_2") (class "Default")
      (node (ref "N4") (pin "K3") (pinfunction "3_K3") (pintype "bidirectional"))
      (node (ref "T42") (pin "3") (pinfunction "C_3") (pintype "passive"))
    )
    (net (code "134") (name "/N4_3") (class "Default")
      (node (ref "N4") (pin "K2") (pinfunction "2_K2") (pintype "bidirectional"))
      (node (ref "T43") (pin "3") (pinfunction "C_3") (pintype "passive"))
    )
    (net (code "135") (name "/N4_4") (class "Default")
      (node (ref "N4") (pin "K0") (pinfunction "0_K0") (pintype "bidirectional"))
      (node (ref "T44") (pin "3") (pinfunction "C_3") (pintype "passive"))
    )
    (net (code "136") (name "/N4_5") (class "Default")
      (node (ref "N4") (pin "K1") (pinfunction "1_K1") (pintype "bidirectional"))
      (node (ref "T45") (pin "3") (pinfunction "C_3") (pintype "passive"))
    )
    (net (code "137") (name "/N4_6") (class "Default")
      (node (ref "N4") (pin "K9") (pinfunction "9_K9") (pintype "bidirectional"))
      (node (ref "T46") (pin "3") (pinfunction "C_3") (pintype "passive"))
    )
    (net (code "138") (name "/N4_7") (class "Default")
      (node (ref "N4") (pin "K8") (pinfunction "8_K8") (pintype "bidirectional"))
      (node (ref "T47") (pin "3") (pinfunction "C_3") (pintype "passive"))
    )
    (net (code "139") (name "/N4_8") (class "Default")
      (node (ref "N4") (pin "K5") (pinfunction "5_K5") (pintype "bidirectional"))
      (node (ref "T48") (pin "3") (pinfunction "C_3") (pintype "passive"))
    )
    (net (code "140") (name "/N4_9") (class "Default")
      (node (ref "N4") (pin "K7") (pinfunction "7_K7") (pintype "bidirectional"))
      (node (ref "T49") (pin "3") (pinfunction "C_3") (pintype "passive"))
    )
    (net (code "141") (name "/N4_DP") (class "Default")
      (node (ref "N4") (pin "KDP") (pinfunction "DP_KDP") (pintype "bidirectional"))
      (node (ref "T4DP") (pin "3") (pinfunction "C_3") (pintype "passive"))
    )
    (net (code "142") (name "/RCK") (class "Default")
      (node (ref "IC1") (pin "12") (pinfunction "RCK_12") (pintype "input"))
      (node (ref "IC2") (pin "12") (pinfunction "RCK_12") (pintype "input"))
      (node (ref "IC3") (pin "12") (pinfunction "RCK_12") (pintype "input"))
      (node (ref "IC4") (pin "12") (pinfunction "RCK_12") (pintype "input"))
      (node (ref "IC5") (pin "12") (pinfunction "RCK_12") (pintype "input"))
      (node (ref "IC6") (pin "12") (pinfunction "RCK_12") (pintype "input"))
      (node (ref "JP1") (pin "9") (pinfunction "9_9") (pintype "passive"))
    )
    (net (code "143") (name "/SCK") (class "Default")
      (node (ref "IC1") (pin "11") (pinfunction "SCK_11") (pintype "input"))
      (node (ref "IC2") (pin "11") (pinfunction "SCK_11") (pintype "input"))
      (node (ref "IC3") (pin "11") (pinfunction "SCK_11") (pintype "input"))
      (node (ref "IC4") (pin "11") (pinfunction "SCK_11") (pintype "input"))
      (node (ref "IC5") (pin "11") (pinfunction "SCK_11") (pintype "input"))
      (node (ref "IC6") (pin "11") (pinfunction "SCK_11") (pintype "input"))
      (node (ref "JP1") (pin "10") (pinfunction "10_10") (pintype "passive"))
    )
    (net (code "144") (name "GND") (class "Default")
      (node (ref "C1") (pin "2") (pinfunction "2_2") (pintype "passive"))
      (node (ref "C2") (pin "2") (pinfunction "2_2") (pintype "passive"))
      (node (ref "C3") (pin "2") (pinfunction "2_2") (pintype "passive"))
      (node (ref "C4") (pin "2") (pinfunction "2_2") (pintype "passive"))
      (node (ref "C5") (pin "2") (pinfunction "2_2") (pintype "passive"))
      (node (ref "C6") (pin "2") (pinfunction "2_2") (pintype "passive"))
      (node (ref "IC1") (pin "8") (pinfunction "GND_8") (pintype "power_in"))
      (node (ref "IC2") (pin "8") (pinfunction "GND_8") (pintype "power_in"))
      (node (ref "IC3") (pin "8") (pinfunction "GND_8") (pintype "power_in"))
      (node (ref "IC4") (pin "8") (pinfunction "GND_8") (pintype "power_in"))
      (node (ref "IC5") (pin "8") (pinfunction "GND_8") (pintype "power_in"))
      (node (ref "IC6") (pin "8") (pinfunction "GND_8") (pintype "power_in"))
      (node (ref "JP1") (pin "2") (pinfunction "2_2") (pintype "passive"))
      (node (ref "JP1") (pin "3") (pinfunction "3_3") (pintype "passive"))
      (node (ref "JP1") (pin "4") (pinfunction "4_4") (pintype "passive"))
      (node (ref "JP1") (pin "5") (pinfunction "5_5") (pintype "passive"))
      (node (ref "T1") (pin "2") (pinfunction "E_2") (pintype "passive"))
      (node (ref "T10") (pin "2") (pinfunction "E_2") (pintype "passive"))
      (node (ref "T11") (pin "2") (pinfunction "E_2") (pintype "passive"))
      (node (ref "T12") (pin "2") (pinfunction "E_2") (pintype "passive"))
      (node (ref "T13") (pin "2") (pinfunction "E_2") (pintype "passive"))
      (node (ref "T14") (pin "2") (pinfunction "E_2") (pintype "passive"))
      (node (ref "T15") (pin "2") (pinfunction "E_2") (pintype "passive"))
      (node (ref "T16") (pin "2") (pinfunction "E_2") (pintype "passive"))
      (node (ref "T17") (pin "2") (pinfunction "E_2") (pintype "passive"))
      (node (ref "T18") (pin "2") (pinfunction "E_2") (pintype "passive"))
      (node (ref "T19") (pin "2") (pinfunction "E_2") (pintype "passive"))
      (node (ref "T1DP") (pin "2") (pinfunction "E_2") (pintype "passive"))
      (node (ref "T2") (pin "2") (pinfunction "E_2") (pintype "passive"))
      (node (ref "T20") (pin "2") (pinfunction "E_2") (pintype "passive"))
      (node (ref "T21") (pin "2") (pinfunction "E_2") (pintype "passive"))
      (node (ref "T22") (pin "2") (pinfunction "E_2") (pintype "passive"))
      (node (ref "T23") (pin "2") (pinfunction "E_2") (pintype "passive"))
      (node (ref "T24") (pin "2") (pinfunction "E_2") (pintype "passive"))
      (node (ref "T25") (pin "2") (pinfunction "E_2") (pintype "passive"))
      (node (ref "T26") (pin "2") (pinfunction "E_2") (pintype "passive"))
      (node (ref "T27") (pin "2") (pinfunction "E_2") (pintype "passive"))
      (node (ref "T28") (pin "2") (pinfunction "E_2") (pintype "passive"))
      (node (ref "T29") (pin "2") (pinfunction "E_2") (pintype "passive"))
      (node (ref "T2DP") (pin "2") (pinfunction "E_2") (pintype "passive"))
      (node (ref "T30") (pin "2") (pinfunction "E_2") (pintype "passive"))
      (node (ref "T31") (pin "2") (pinfunction "E_2") (pintype "passive"))
      (node (ref "T32") (pin "2") (pinfunction "E_2") (pintype "passive"))
      (node (ref "T33") (pin "2") (pinfunction "E_2") (pintype "passive"))
      (node (ref "T34") (pin "2") (pinfunction "E_2") (pintype "passive"))
      (node (ref "T35") (pin "2") (pinfunction "E_2") (pintype "passive"))
      (node (ref "T36") (pin "2") (pinfunction "E_2") (pintype "passive"))
      (node (ref "T37") (pin "2") (pinfunction "E_2") (pintype "passive"))
      (node (ref "T38") (pin "2") (pinfunction "E_2") (pintype "passive"))
      (node (ref "T39") (pin "2") (pinfunction "E_2") (pintype "passive"))
      (node (ref "T3DP") (pin "2") (pinfunction "E_2") (pintype "passive"))
      (node (ref "T40") (pin "2") (pinfunction "E_2") (pintype "passive"))
      (node (ref "T41") (pin "2") (pinfunction "E_2") (pintype "passive"))
      (node (ref "T42") (pin "2") (pinfunction "E_2") (pintype "passive"))
      (node (ref "T43") (pin "2") (pinfunction "E_2") (pintype "passive"))
      (node (ref "T44") (pin "2") (pinfunction "E_2") (pintype "passive"))
      (node (ref "T45") (pin "2") (pinfunction "E_2") (pintype "passive"))
      (node (ref "T46") (pin "2") (pinfunction "E_2") (pintype "passive"))
      (node (ref "T47") (pin "2") (pinfunction "E_2") (pintype "passive"))
      (node (ref "T48") (pin "2") (pinfunction "E_2") (pintype "passive"))
      (node (ref "T49") (pin "2") (pinfunction "E_2") (pintype "passive"))
      (node (ref "T4DP") (pin "2") (pinfunction "E_2") (pintype "passive"))
    )
    (net (code "145") (name "Net-(GL1-A)") (class "Default")
      (node (ref "GL1") (pin "1") (pinfunction "A_1") (pintype "passive"))
      (node (ref "R1") (pin "1") (pinfunction "1_1") (pintype "passive"))
    )
    (net (code "146") (name "Net-(GL1-A1)") (class "Default")
      (node (ref "GL1") (pin "2") (pinfunction "A1_2") (pintype "passive"))
      (node (ref "T1") (pin "3") (pinfunction "C_3") (pintype "passive"))
    )
    (net (code "147") (name "Net-(GL2-A)") (class "Default")
      (node (ref "GL2") (pin "1") (pinfunction "A_1") (pintype "passive"))
      (node (ref "R2") (pin "1") (pinfunction "1_1") (pintype "passive"))
    )
    (net (code "148") (name "Net-(GL2-A1)") (class "Default")
      (node (ref "GL2") (pin "2") (pinfunction "A1_2") (pintype "passive"))
      (node (ref "T2") (pin "3") (pinfunction "C_3") (pintype "passive"))
    )
    (net (code "149") (name "Net-(IC1A-QH*)") (class "Default")
      (node (ref "IC1") (pin "9") (pinfunction "QH*_9") (pintype "tri_state"))
      (node (ref "IC2") (pin "14") (pinfunction "SER_14") (pintype "input"))
    )
    (net (code "150") (name "Net-(IC2A-QH*)") (class "Default")
      (node (ref "IC2") (pin "9") (pinfunction "QH*_9") (pintype "tri_state"))
      (node (ref "IC3") (pin "14") (pinfunction "SER_14") (pintype "input"))
    )
    (net (code "151") (name "Net-(IC3A-QH*)") (class "Default")
      (node (ref "IC3") (pin "9") (pinfunction "QH*_9") (pintype "tri_state"))
      (node (ref "IC4") (pin "14") (pinfunction "SER_14") (pintype "input"))
    )
    (net (code "152") (name "Net-(IC4A-QH*)") (class "Default")
      (node (ref "IC4") (pin "9") (pinfunction "QH*_9") (pintype "tri_state"))
      (node (ref "IC5") (pin "14") (pinfunction "SER_14") (pintype "input"))
    )
    (net (code "153") (name "Net-(IC5A-QH*)") (class "Default")
      (node (ref "IC5") (pin "9") (pinfunction "QH*_9") (pintype "tri_state"))
      (node (ref "IC6") (pin "14") (pinfunction "SER_14") (pintype "input"))
    )
    (net (code "154") (name "Net-(N1-PadA)") (class "Default")
      (node (ref "N1") (pin "A") (pinfunction "A_A") (pintype "bidirectional"))
      (node (ref "R10") (pin "1") (pinfunction "1_1") (pintype "passive"))
    )
    (net (code "155") (name "Net-(N2-PadA)") (class "Default")
      (node (ref "N2") (pin "A") (pinfunction "A_A") (pintype "bidirectional"))
      (node (ref "R20") (pin "1") (pinfunction "1_1") (pintype "passive"))
    )
    (net (code "156") (name "Net-(N3-PadA)") (class "Default")
      (node (ref "N3") (pin "A") (pinfunction "A_A") (pintype "bidirectional"))
      (node (ref "R30") (pin "1") (pinfunction "1_1") (pintype "passive"))
    )
    (net (code "157") (name "Net-(N4-PadA)") (class "Default")
      (node (ref "N4") (pin "A") (pinfunction "A_A") (pintype "bidirectional"))
      (node (ref "R40") (pin "1") (pinfunction "1_1") (pintype "passive"))
    )
    (net (code "158") (name "VDD") (class "Default")
      (node (ref "JP1") (pin "1") (pinfunction "1_1") (pintype "passive"))
      (node (ref "R1") (pin "2") (pinfunction "2_2") (pintype "passive"))
      (node (ref "R10") (pin "2") (pinfunction "2_2") (pintype "passive"))
      (node (ref "R2") (pin "2") (pinfunction "2_2") (pintype "passive"))
      (node (ref "R20") (pin "2") (pinfunction "2_2") (pintype "passive"))
      (node (ref "R30") (pin "2") (pinfunction "2_2") (pintype "passive"))
      (node (ref "R40") (pin "2") (pinfunction "2_2") (pintype "passive"))
    )
    (net (code "159") (name "unconnected-(IC6A-QH*-Pad9)") (class "Default")
      (node (ref "IC6") (pin "9") (pinfunction "QH*_9") (pintype "tri_state"))
    )
    (net (code "160") (name "unconnected-(RN61-Pad7)") (class "Default")
      (node (ref "RN61") (pin "7") (pinfunction "7_7") (pintype "passive"))
    )
    (net (code "161") (name "unconnected-(RN61-Pad8)") (class "Default")
      (node (ref "RN61") (pin "8") (pinfunction "8_8") (pintype "passive"))
    )
  )
)
